# nrf52840_v2.net
KiCad netlist of a schematic drawn in Altium Designer
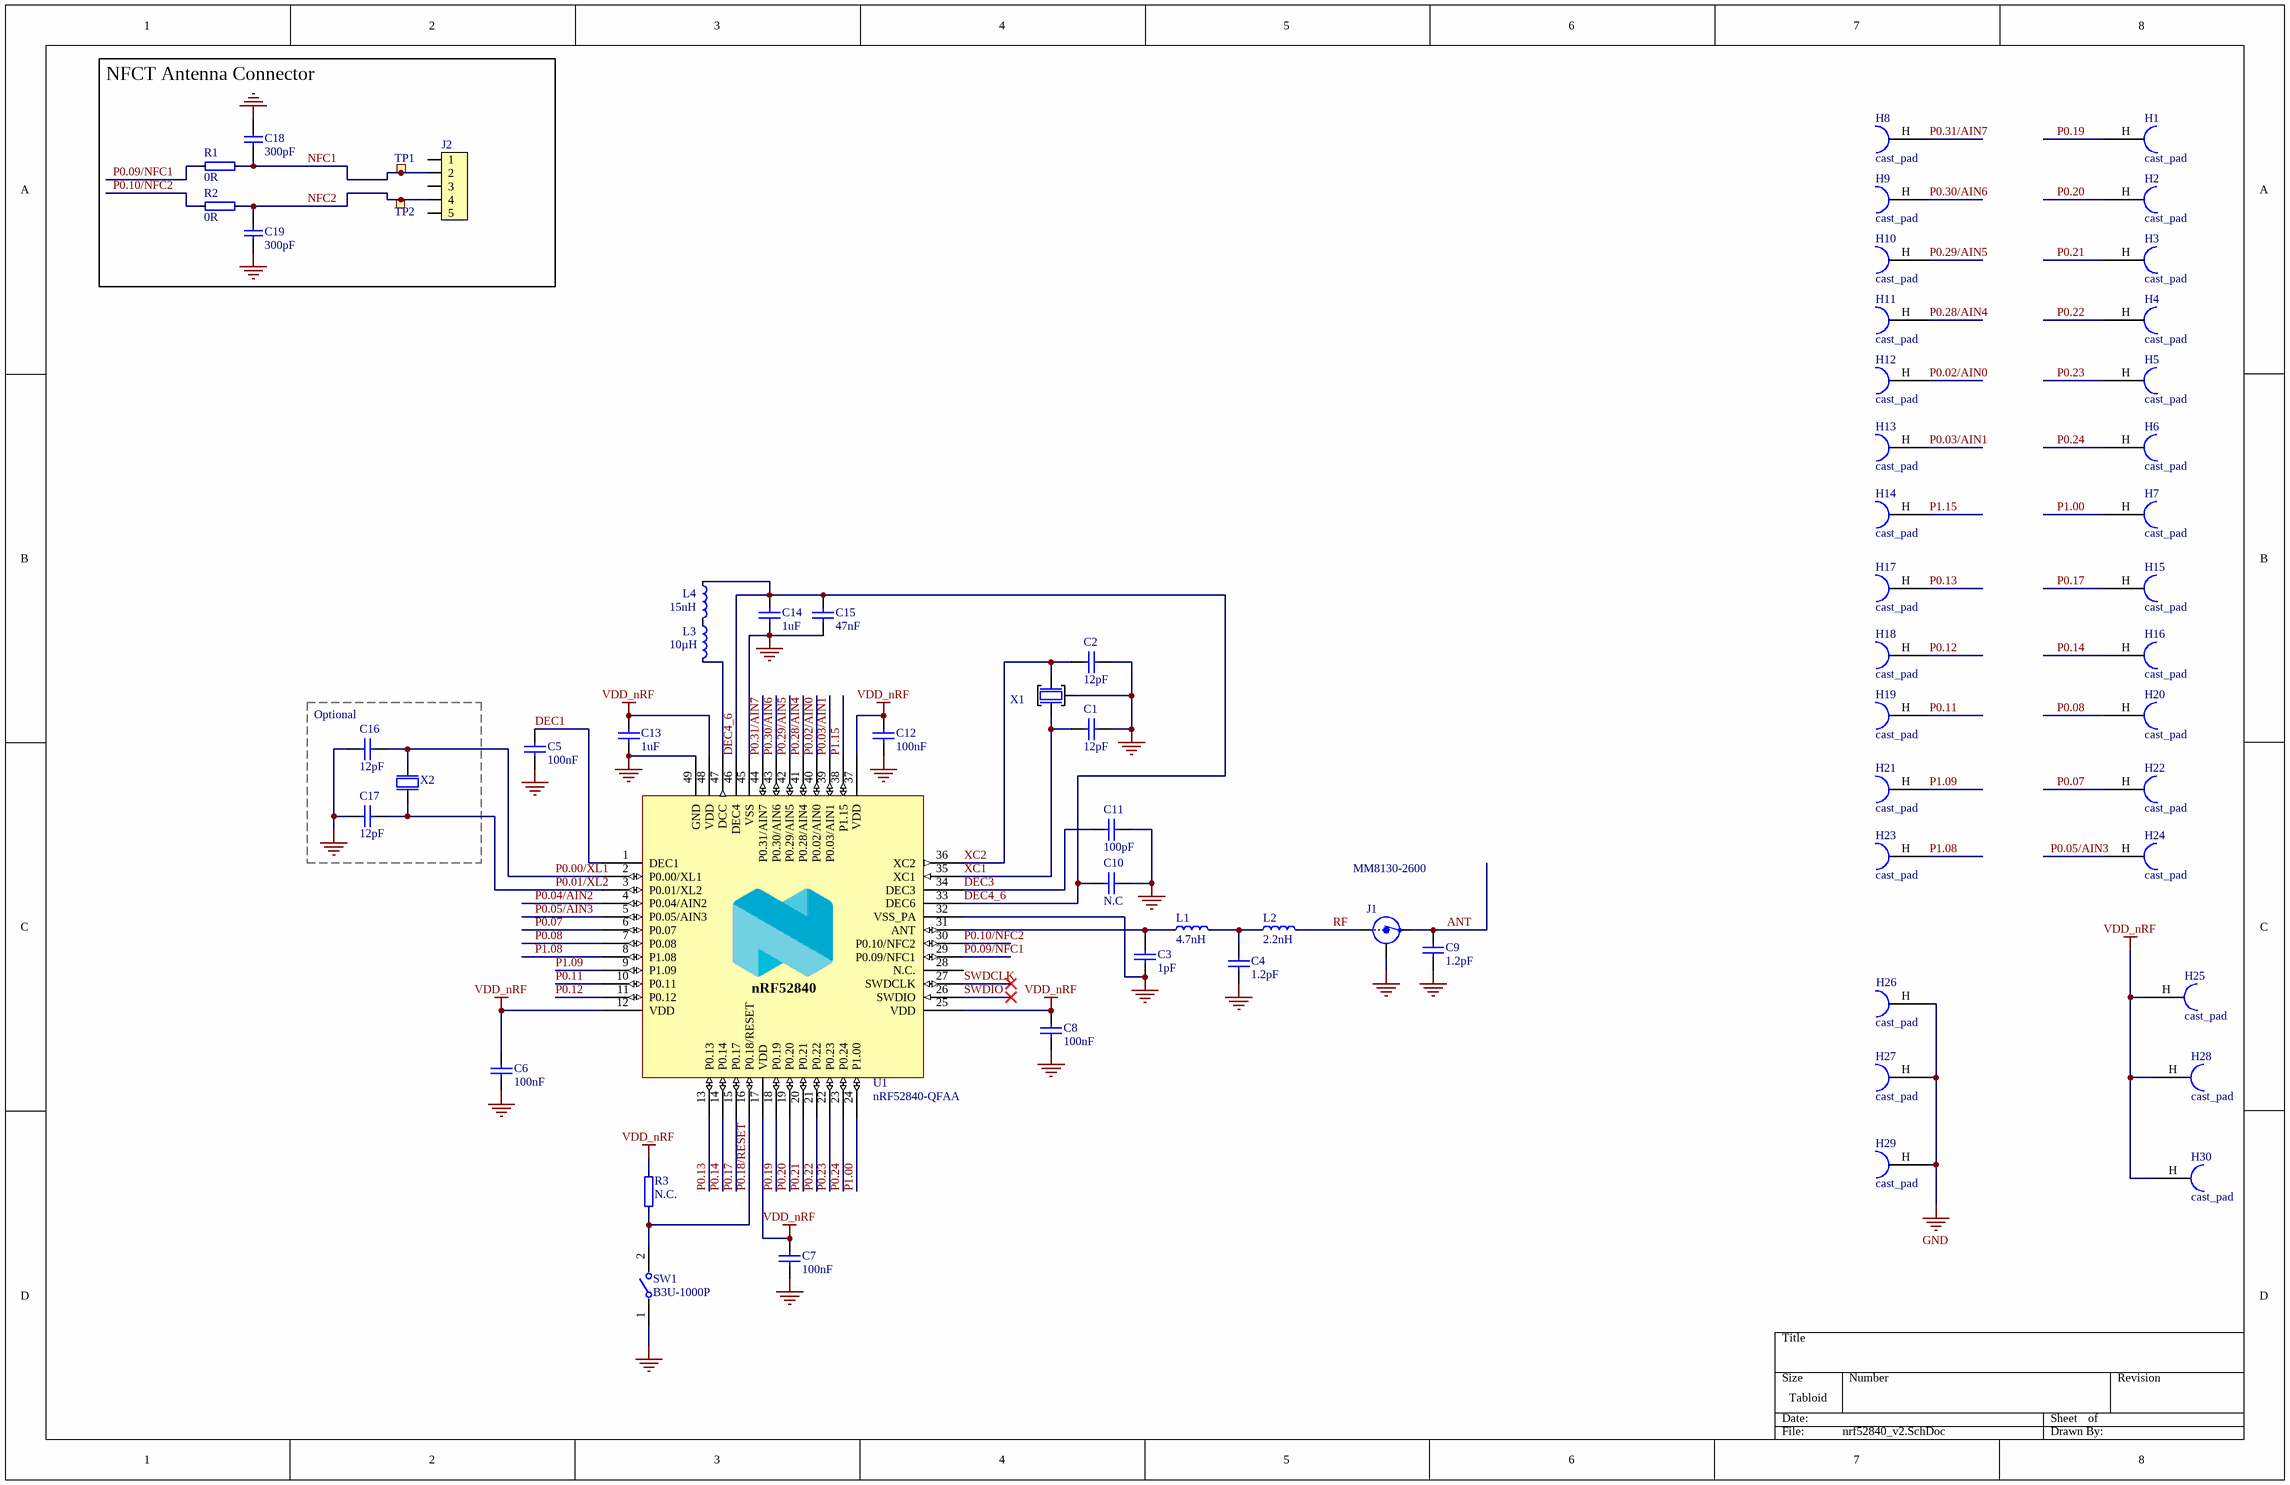
[diagram p0: nrf52840_v2.SchDoc]

(export (version "E")
  (design (tool "Eeschema 10.0.6"))
  (components
    (comp (ref "C1")
      (value "12pF")
      (footprint "CAPC1005X55X30LL05T10")
      (fields (field (name "PART NUMBER") "C0402C103K5RACTU") (field (name "MANUFACTURER") "Kemet"))
      (libsource (lib "Altium Content Vault") (part "CAP"))
    )
    (comp (ref "C2")
      (value "12pF")
      (footprint "CAPC1005X55X30LL05T10")
      (fields (field (name "PART NUMBER") "C0402C103K5RACTU") (field (name "MANUFACTURER") "Kemet"))
      (libsource (lib "Altium Content Vault") (part "CAP"))
    )
    (comp (ref "C3")
      (value "1pF")
      (footprint "CAPC1005X55X30LL05T10")
      (fields (field (name "PART NUMBER") "C0402C103K5RACTU") (field (name "MANUFACTURER") "Kemet"))
      (libsource (lib "Altium Content Vault") (part "CAP"))
    )
    (comp (ref "C4")
      (value "1.2pF")
      (footprint "CAPC1005X55X30LL05T10")
      (fields (field (name "PART NUMBER") "C0402C103K5RACTU") (field (name "MANUFACTURER") "Kemet"))
      (libsource (lib "Altium Content Vault") (part "CAP"))
    )
    (comp (ref "C5")
      (value "100nF")
      (footprint "CAPC1005X55X30LL05T10")
      (fields (field (name "PART NUMBER") "C0402C103K5RACTU") (field (name "MANUFACTURER") "Kemet"))
      (libsource (lib "Altium Content Vault") (part "CAP"))
    )
    (comp (ref "C6")
      (value "100nF")
      (footprint "CAPC1005X55X30LL05T10")
      (fields (field (name "PART NUMBER") "C0402C103K5RACTU") (field (name "MANUFACTURER") "Kemet"))
      (libsource (lib "Altium Content Vault") (part "CAP"))
    )
    (comp (ref "C7")
      (value "100nF")
      (footprint "CAPC1005X55X30LL05T10")
      (fields (field (name "PART NUMBER") "C0402C103K5RACTU") (field (name "MANUFACTURER") "Kemet"))
      (libsource (lib "Altium Content Vault") (part "CAP"))
    )
    (comp (ref "C8")
      (value "100nF")
      (footprint "CAPC1005X55X30LL05T10")
      (fields (field (name "PART NUMBER") "C0402C103K5RACTU") (field (name "MANUFACTURER") "Kemet"))
      (libsource (lib "Altium Content Vault") (part "CAP"))
    )
    (comp (ref "C9")
      (value "1.2pF")
      (footprint "CAPC1005X55X30LL05T10")
      (fields (field (name "PART NUMBER") "C0402C103K5RACTU") (field (name "MANUFACTURER") "Kemet"))
      (libsource (lib "Altium Content Vault") (part "CAP"))
    )
    (comp (ref "C10")
      (value "N.C")
      (footprint "CAPC1005X55X30LL05T10")
      (fields (field (name "PART NUMBER") "C0402C103K5RACTU") (field (name "MANUFACTURER") "Kemet"))
      (libsource (lib "Altium Content Vault") (part "CAP"))
    )
    (comp (ref "C11")
      (value "100pF")
      (footprint "CAPC1005X55X30LL05T10")
      (fields (field (name "PART NUMBER") "C0402C103K5RACTU") (field (name "MANUFACTURER") "Kemet"))
      (libsource (lib "Altium Content Vault") (part "CAP"))
    )
    (comp (ref "C12")
      (value "100nF")
      (footprint "CAPC1005X55X30LL05T10")
      (fields (field (name "PART NUMBER") "C0402C103K5RACTU") (field (name "MANUFACTURER") "Kemet"))
      (libsource (lib "Altium Content Vault") (part "CAP"))
    )
    (comp (ref "C13")
      (value "1uF")
      (footprint "CAPC1005X55X30LL05T10")
      (fields (field (name "PART NUMBER") "C0402C103K5RACTU") (field (name "MANUFACTURER") "Kemet"))
      (libsource (lib "Altium Content Vault") (part "CAP"))
    )
    (comp (ref "C14")
      (value "1uF")
      (footprint "CAPC1005X55X30LL05T10")
      (fields (field (name "PART NUMBER") "C0402C103K5RACTU") (field (name "MANUFACTURER") "Kemet"))
      (libsource (lib "Altium Content Vault") (part "CAP"))
    )
    (comp (ref "C15")
      (value "47nF")
      (footprint "CAPC1005X55X30LL05T10")
      (fields (field (name "PART NUMBER") "C0402C103K5RACTU") (field (name "MANUFACTURER") "Kemet"))
      (libsource (lib "Altium Content Vault") (part "CAP"))
    )
    (comp (ref "C16")
      (value "12pF")
      (footprint "CAPC1005X55X30LL05T10")
      (fields (field (name "PART NUMBER") "C0402C103K5RACTU") (field (name "MANUFACTURER") "Kemet"))
      (libsource (lib "Altium Content Vault") (part "CAP"))
    )
    (comp (ref "C17")
      (value "12pF")
      (footprint "CAPC1005X55X30LL05T10")
      (fields (field (name "PART NUMBER") "C0402C103K5RACTU") (field (name "MANUFACTURER") "Kemet"))
      (libsource (lib "Altium Content Vault") (part "CAP"))
    )
    (comp (ref "C18")
      (value "300pF")
      (footprint "CAPC1005X04L")
      (description "Capacitor, NP0, ±5%")
      (fields
        (field (name "PART NUMBER") "C0402-300p")
        (field (name "MANUFACTURER") "N.A.")
        (field (name "PUBLISHER") "Nordic Semiconductor")
        (field (name "AUTHOR") "rsk")
      )
      (libsource (lib "pca10056") (part "CAP"))
    )
    (comp (ref "C19")
      (value "300pF")
      (footprint "CAPC1005X04L")
      (description "Capacitor, NP0, ±5%")
      (fields
        (field (name "PART NUMBER") "C0402-300p")
        (field (name "MANUFACTURER") "N.A.")
        (field (name "PUBLISHER") "Nordic Semiconductor")
        (field (name "AUTHOR") "rsk")
      )
      (libsource (lib "pca10056") (part "CAP"))
    )
    (comp (ref "H1")
      (value "cast_pad")
      (footprint "cast_pad")
      (libsource (lib "castellated_pads") (part "cast_pad"))
    )
    (comp (ref "H2")
      (value "cast_pad")
      (footprint "cast_pad")
      (libsource (lib "castellated_pads") (part "cast_pad"))
    )
    (comp (ref "H3")
      (value "cast_pad")
      (footprint "cast_pad")
      (libsource (lib "castellated_pads") (part "cast_pad"))
    )
    (comp (ref "H4")
      (value "cast_pad")
      (footprint "cast_pad")
      (libsource (lib "castellated_pads") (part "cast_pad"))
    )
    (comp (ref "H5")
      (value "cast_pad")
      (footprint "cast_pad")
      (libsource (lib "castellated_pads") (part "cast_pad"))
    )
    (comp (ref "H6")
      (value "cast_pad")
      (footprint "cast_pad")
      (libsource (lib "castellated_pads") (part "cast_pad"))
    )
    (comp (ref "H7")
      (value "cast_pad")
      (footprint "cast_pad")
      (libsource (lib "castellated_pads") (part "cast_pad"))
    )
    (comp (ref "H8")
      (value "cast_pad")
      (footprint "cast_pad")
      (libsource (lib "castellated_pads") (part "cast_pad"))
    )
    (comp (ref "H9")
      (value "cast_pad")
      (footprint "cast_pad")
      (libsource (lib "castellated_pads") (part "cast_pad"))
    )
    (comp (ref "H10")
      (value "cast_pad")
      (footprint "cast_pad")
      (libsource (lib "castellated_pads") (part "cast_pad"))
    )
    (comp (ref "H11")
      (value "cast_pad")
      (footprint "cast_pad")
      (libsource (lib "castellated_pads") (part "cast_pad"))
    )
    (comp (ref "H12")
      (value "cast_pad")
      (footprint "cast_pad")
      (libsource (lib "castellated_pads") (part "cast_pad"))
    )
    (comp (ref "H13")
      (value "cast_pad")
      (footprint "cast_pad")
      (libsource (lib "castellated_pads") (part "cast_pad"))
    )
    (comp (ref "H14")
      (value "cast_pad")
      (footprint "cast_pad")
      (libsource (lib "castellated_pads") (part "cast_pad"))
    )
    (comp (ref "H15")
      (value "cast_pad")
      (footprint "cast_pad")
      (libsource (lib "castellated_pads") (part "cast_pad"))
    )
    (comp (ref "H16")
      (value "cast_pad")
      (footprint "cast_pad")
      (libsource (lib "castellated_pads") (part "cast_pad"))
    )
    (comp (ref "H17")
      (value "cast_pad")
      (footprint "cast_pad")
      (libsource (lib "castellated_pads") (part "cast_pad"))
    )
    (comp (ref "H18")
      (value "cast_pad")
      (footprint "cast_pad")
      (libsource (lib "castellated_pads") (part "cast_pad"))
    )
    (comp (ref "H19")
      (value "cast_pad")
      (footprint "cast_pad")
      (libsource (lib "castellated_pads") (part "cast_pad"))
    )
    (comp (ref "H20")
      (value "cast_pad")
      (footprint "cast_pad")
      (libsource (lib "castellated_pads") (part "cast_pad"))
    )
    (comp (ref "H21")
      (value "cast_pad")
      (footprint "cast_pad")
      (libsource (lib "castellated_pads") (part "cast_pad"))
    )
    (comp (ref "H22")
      (value "cast_pad")
      (footprint "cast_pad")
      (libsource (lib "castellated_pads") (part "cast_pad"))
    )
    (comp (ref "H23")
      (value "cast_pad")
      (footprint "cast_pad")
      (libsource (lib "castellated_pads") (part "cast_pad"))
    )
    (comp (ref "H24")
      (value "cast_pad")
      (footprint "cast_pad")
      (libsource (lib "castellated_pads") (part "cast_pad"))
    )
    (comp (ref "H25")
      (value "cast_pad")
      (footprint "cast_pad")
      (libsource (lib "castellated_pads") (part "cast_pad"))
    )
    (comp (ref "H26")
      (value "cast_pad")
      (footprint "cast_pad")
      (libsource (lib "castellated_pads") (part "cast_pad"))
    )
    (comp (ref "H27")
      (value "cast_pad")
      (footprint "cast_pad")
      (libsource (lib "castellated_pads") (part "cast_pad"))
    )
    (comp (ref "H28")
      (value "cast_pad")
      (footprint "cast_pad")
      (libsource (lib "castellated_pads") (part "cast_pad"))
    )
    (comp (ref "H29")
      (value "cast_pad")
      (footprint "cast_pad")
      (libsource (lib "castellated_pads") (part "cast_pad"))
    )
    (comp (ref "H30")
      (value "cast_pad")
      (footprint "cast_pad")
      (libsource (lib "castellated_pads") (part "cast_pad"))
    )
    (comp (ref "J1")
      (value "MM8130-2600")
      (footprint "COAXIAL-SWF")
      (description "Coaxial Connector with Switch")
      (fields
        (field (name "MANUFACTURER") "Murata")
        (field (name "PUBLISHER") "Nordic Semiconductor")
        (field (name "AUTHOR") "rsk")
      )
      (libsource (lib "pca10056") (part "MM8130-2600"))
    )
    (comp (ref "J2")
      (value "~")
      (footprint "FPC_05P-0.5mm-RA-SMD")
      (description "0.5mm FPC, 5P,Right Angle SMT,Double Contact,H=1.2mm,White, Tin plated")
      (fields
        (field (name "PART NUMBER") "FPC_05P-0.5mm-RA-SMD")
        (field (name "MANUFACTURER") "W-CON")
        (field (name "PUBLISHER") "Nordic Semiconductor")
        (field (name "AUTHOR") "rsk")
      )
      (libsource (lib "pca10056") (part "CONN-5"))
    )
    (comp (ref "L1")
      (value "4.7nH")
      (footprint "INDC0603X03L_C")
      (description "High frequency chip inductor ±5%")
      (fields (field (name "PART NUMBER") "L0201-4n7"))
      (libsource (lib "nrf52840_qfaa") (part "IND"))
    )
    (comp (ref "L2")
      (value "2.2nH")
      (footprint "INDC0603X03L_C")
      (description "High frequency chip inductor ±5%")
      (fields (field (name "PART NUMBER") "L0201-2n2"))
      (libsource (lib "nrf52840_qfaa") (part "IND"))
    )
    (comp (ref "L3")
      (value "10µH")
      (footprint "INDC1608X06L")
      (description "Chip inductor, IDC,min = 50 mA, ±20%")
      (fields (field (name "PART NUMBER") "L0603-10µ-TDK"))
      (libsource (lib "nrf52840_qfaa") (part "IND"))
    )
    (comp (ref "L4")
      (value "15nH")
      (footprint "INDC1005X04L")
      (description "High frequency chip inductor ±10%")
      (fields (field (name "PART NUMBER") "L0402-15n"))
      (libsource (lib "nrf52840_qfaa") (part "IND"))
    )
    (comp (ref "R1")
      (value "0R")
      (footprint "RESC1005X04L")
      (description "Resistor, ±5%, 0.063W")
      (fields
        (field (name "PART NUMBER") "R0402-0R")
        (field (name "MANUFACTURER") "N.A.")
        (field (name "PUBLISHER") "Nordic Semiconductor")
        (field (name "AUTHOR") "rsk")
      )
      (libsource (lib "pca10056") (part "RES_1"))
    )
    (comp (ref "R2")
      (value "0R")
      (footprint "RESC1005X04L")
      (description "Resistor, ±5%, 0.063W")
      (fields
        (field (name "PART NUMBER") "R0402-0R")
        (field (name "MANUFACTURER") "N.A.")
        (field (name "PUBLISHER") "Nordic Semiconductor")
        (field (name "AUTHOR") "rsk")
      )
      (libsource (lib "pca10056") (part "RES_1"))
    )
    (comp (ref "R3")
      (value "N.C.")
      (footprint "RESC1005X04L")
      (description "Not mounted")
      (fields
        (field (name "PART NUMBER") "R0402-N.C.")
        (field (name "MANUFACTURER") "N.A.")
        (field (name "PUBLISHER") "Nordic Semiconductor")
        (field (name "AUTHOR") "rsk")
      )
      (libsource (lib "pca10056") (part "R0402-N.C."))
    )
    (comp (ref "SW1")
      (value "B3U-1000P")
      (footprint "FP-B3U-1000P-MFG")
      (description "SWITCH TACTILE SPST-NO 0.05A 12V")
      (libsource (lib "Altium Content Vault") (part "ae622034201233ca1abcedc05908f33"))
    )
    (comp (ref "TP1")
      (value "Ø1.0mm,SMD")
      (footprint "TP_SMD_Ø1.0mm")
      (description "1.0mm circular SMD testpad")
      (fields
        (field (name "PART NUMBER") "TP_SMD_Ø1.0MM")
        (field (name "MANUFACTURER") "Nordic Semiconductor")
        (field (name "PUBLISHER") "Nordic Semiconductor")
        (field (name "AUTHOR") "rsk")
      )
      (libsource (lib "") (part "TESTPAD_1"))
    )
    (comp (ref "TP2")
      (value "Ø1.0mm,SMD")
      (footprint "TP_SMD_Ø1.0mm")
      (description "1.0mm circular SMD testpad")
      (fields
        (field (name "PART NUMBER") "TP_SMD_Ø1.0MM")
        (field (name "MANUFACTURER") "Nordic Semiconductor")
        (field (name "PUBLISHER") "Nordic Semiconductor")
        (field (name "AUTHOR") "rsk")
      )
      (libsource (lib "pca10056") (part "TESTPAD"))
    )
    (comp (ref "U1")
      (value "nRF52840-QFAA")
      (footprint "QFN40P600X600X90-48N")
      (description "Multi-protocol Bluetooth Low Energy, IEEE 802.15.4, ANT and 2.4GHz proprietary system-on-chip")
      (libsource (lib "nrf52840_qfaa") (part "nRF52840_QFAA"))
    )
    (comp (ref "X1")
      (value "~")
      (footprint "XTAL_2016_NT")
      (description "XTAL SMD 2016, 32MHz, Cl=8pF, Total Tol: ±30ppm")
      (fields (field (name "PART NUMBER") "XTAL_SMD2016_32MHz_8pF_General_NT"))
      (libsource (lib "nrf52840_qfaa") (part "XTAL_4-pin_NT"))
    )
    (comp (ref "X2")
      (value "~")
      (footprint "XTAL_2012")
      (description "XTAL SMD 2012, 32.768kHz, Cl=9pF, Total Tol: ±50ppm")
      (fields (field (name "PART NUMBER") "XTAL_SMD2012_32.768kHz_9pF_General"))
      (libsource (lib "nrf52840_qfaa") (part "XTAL_2-pin"))
    )
  )
  (nets
    (net (code "1") (name "/ANT") (class "Default")
      (node (ref "C9") (pin "2") (pinfunction "2_2") (pintype "passive"))
      (node (ref "J1") (pin "3") (pinfunction "OUT_3") (pintype "passive"))
    )
    (net (code "2") (name "/DEC1") (class "Default")
      (node (ref "C5") (pin "2") (pinfunction "2_2") (pintype "passive"))
      (node (ref "U1") (pin "1") (pinfunction "DEC1_1") (pintype "power_in"))
    )
    (net (code "3") (name "/DEC3") (class "Default")
      (node (ref "C11") (pin "1") (pinfunction "1_1") (pintype "passive"))
      (node (ref "U1") (pin "34") (pinfunction "DEC3_34") (pintype "power_in"))
    )
    (net (code "4") (name "/DEC4_6") (class "Default")
      (node (ref "C10") (pin "1") (pinfunction "1_1") (pintype "passive"))
      (node (ref "C14") (pin "2") (pinfunction "2_2") (pintype "passive"))
      (node (ref "C15") (pin "2") (pinfunction "2_2") (pintype "passive"))
      (node (ref "L4") (pin "1") (pinfunction "1_1") (pintype "passive"))
      (node (ref "U1") (pin "33") (pinfunction "DEC6_33") (pintype "power_in"))
      (node (ref "U1") (pin "46") (pinfunction "DEC4_46") (pintype "power_in"))
    )
    (net (code "5") (name "/NFC1") (class "Default")
      (node (ref "C18") (pin "1") (pinfunction "1_1") (pintype "passive"))
      (node (ref "J2") (pin "2") (pinfunction "2_2") (pintype "passive"))
      (node (ref "R1") (pin "1") (pinfunction "1_1") (pintype "passive"))
      (node (ref "TP1") (pin "1") (pinfunction "1_1") (pintype "passive"))
    )
    (net (code "6") (name "/NFC2") (class "Default")
      (node (ref "C19") (pin "2") (pinfunction "2_2") (pintype "passive"))
      (node (ref "J2") (pin "4") (pinfunction "4_4") (pintype "passive"))
      (node (ref "R2") (pin "1") (pinfunction "1_1") (pintype "passive"))
      (node (ref "TP2") (pin "1") (pinfunction "1_1") (pintype "passive"))
    )
    (net (code "7") (name "/P0.00{slash}XL1") (class "Default")
      (node (ref "C16") (pin "2") (pinfunction "2_2") (pintype "passive"))
      (node (ref "U1") (pin "2") (pinfunction "P0.00/XL1_2") (pintype "bidirectional"))
      (node (ref "X2") (pin "1") (pinfunction "inp_1") (pintype "passive"))
    )
    (net (code "8") (name "/P0.01{slash}XL2") (class "Default")
      (node (ref "C17") (pin "2") (pinfunction "2_2") (pintype "passive"))
      (node (ref "U1") (pin "3") (pinfunction "P0.01/XL2_3") (pintype "bidirectional"))
      (node (ref "X2") (pin "2") (pinfunction "out_2") (pintype "passive"))
    )
    (net (code "9") (name "/P0.02{slash}AIN0") (class "Default")
      (node (ref "H12") (pin "H") (pintype "passive"))
      (node (ref "U1") (pin "40") (pinfunction "P0.02/AIN0_40") (pintype "bidirectional"))
    )
    (net (code "10") (name "/P0.03{slash}AIN1") (class "Default")
      (node (ref "H13") (pin "H") (pintype "passive"))
      (node (ref "U1") (pin "39") (pinfunction "P0.03/AIN1_39") (pintype "bidirectional"))
    )
    (net (code "11") (name "/P0.04{slash}AIN2") (class "Default")
      (node (ref "U1") (pin "4") (pinfunction "P0.04/AIN2_4") (pintype "bidirectional"))
    )
    (net (code "12") (name "/P0.05{slash}AIN3") (class "Default")
      (node (ref "H24") (pin "H") (pintype "passive"))
      (node (ref "U1") (pin "5") (pinfunction "P0.05/AIN3_5") (pintype "bidirectional"))
    )
    (net (code "13") (name "/P0.07") (class "Default")
      (node (ref "H22") (pin "H") (pintype "passive"))
      (node (ref "U1") (pin "6") (pinfunction "P0.07_6") (pintype "bidirectional"))
    )
    (net (code "14") (name "/P0.08") (class "Default")
      (node (ref "H20") (pin "H") (pintype "passive"))
      (node (ref "U1") (pin "7") (pinfunction "P0.08_7") (pintype "bidirectional"))
    )
    (net (code "15") (name "/P0.09{slash}NFC1") (class "Default")
      (node (ref "R1") (pin "2") (pinfunction "2_2") (pintype "passive"))
      (node (ref "U1") (pin "29") (pinfunction "P0.09/NFC1_29") (pintype "bidirectional"))
    )
    (net (code "16") (name "/P0.10{slash}NFC2") (class "Default")
      (node (ref "R2") (pin "2") (pinfunction "2_2") (pintype "passive"))
      (node (ref "U1") (pin "30") (pinfunction "P0.10/NFC2_30") (pintype "bidirectional"))
    )
    (net (code "17") (name "/P0.11") (class "Default")
      (node (ref "H19") (pin "H") (pintype "passive"))
      (node (ref "U1") (pin "10") (pinfunction "P0.11_10") (pintype "bidirectional"))
    )
    (net (code "18") (name "/P0.12") (class "Default")
      (node (ref "H18") (pin "H") (pintype "passive"))
      (node (ref "U1") (pin "11") (pinfunction "P0.12_11") (pintype "bidirectional"))
    )
    (net (code "19") (name "/P0.13") (class "Default")
      (node (ref "H17") (pin "H") (pintype "passive"))
      (node (ref "U1") (pin "13") (pinfunction "P0.13_13") (pintype "bidirectional"))
    )
    (net (code "20") (name "/P0.14") (class "Default")
      (node (ref "H16") (pin "H") (pintype "passive"))
      (node (ref "U1") (pin "14") (pinfunction "P0.14_14") (pintype "bidirectional"))
    )
    (net (code "21") (name "/P0.17") (class "Default")
      (node (ref "H15") (pin "H") (pintype "passive"))
      (node (ref "U1") (pin "15") (pinfunction "P0.17_15") (pintype "bidirectional"))
    )
    (net (code "22") (name "/P0.18{slash}RESET") (class "Default")
      (node (ref "R3") (pin "1") (pinfunction "1_1") (pintype "passive"))
      (node (ref "SW1") (pin "2") (pinfunction "2_2") (pintype "passive"))
      (node (ref "U1") (pin "16") (pinfunction "P0.18/RESET_16") (pintype "bidirectional"))
    )
    (net (code "23") (name "/P0.19") (class "Default")
      (node (ref "H1") (pin "H") (pintype "passive"))
      (node (ref "U1") (pin "18") (pinfunction "P0.19_18") (pintype "bidirectional"))
    )
    (net (code "24") (name "/P0.20") (class "Default")
      (node (ref "H2") (pin "H") (pintype "passive"))
      (node (ref "U1") (pin "19") (pinfunction "P0.20_19") (pintype "bidirectional"))
    )
    (net (code "25") (name "/P0.21") (class "Default")
      (node (ref "H3") (pin "H") (pintype "passive"))
      (node (ref "U1") (pin "20") (pinfunction "P0.21_20") (pintype "bidirectional"))
    )
    (net (code "26") (name "/P0.22") (class "Default")
      (node (ref "H4") (pin "H") (pintype "passive"))
      (node (ref "U1") (pin "21") (pinfunction "P0.22_21") (pintype "bidirectional"))
    )
    (net (code "27") (name "/P0.23") (class "Default")
      (node (ref "H5") (pin "H") (pintype "passive"))
      (node (ref "U1") (pin "22") (pinfunction "P0.23_22") (pintype "bidirectional"))
    )
    (net (code "28") (name "/P0.24") (class "Default")
      (node (ref "H6") (pin "H") (pintype "passive"))
      (node (ref "U1") (pin "23") (pinfunction "P0.24_23") (pintype "bidirectional"))
    )
    (net (code "29") (name "/P0.28{slash}AIN4") (class "Default")
      (node (ref "H11") (pin "H") (pintype "passive"))
      (node (ref "U1") (pin "41") (pinfunction "P0.28/AIN4_41") (pintype "bidirectional"))
    )
    (net (code "30") (name "/P0.29{slash}AIN5") (class "Default")
      (node (ref "H10") (pin "H") (pintype "passive"))
      (node (ref "U1") (pin "42") (pinfunction "P0.29/AIN5_42") (pintype "bidirectional"))
    )
    (net (code "31") (name "/P0.30{slash}AIN6") (class "Default")
      (node (ref "H9") (pin "H") (pintype "passive"))
      (node (ref "U1") (pin "43") (pinfunction "P0.30/AIN6_43") (pintype "bidirectional"))
    )
    (net (code "32") (name "/P0.31{slash}AIN7") (class "Default")
      (node (ref "H8") (pin "H") (pintype "passive"))
      (node (ref "U1") (pin "44") (pinfunction "P0.31/AIN7_44") (pintype "bidirectional"))
    )
    (net (code "33") (name "/P1.00") (class "Default")
      (node (ref "H7") (pin "H") (pintype "passive"))
      (node (ref "U1") (pin "24") (pinfunction "P1.00_24") (pintype "bidirectional"))
    )
    (net (code "34") (name "/P1.08") (class "Default")
      (node (ref "H23") (pin "H") (pintype "passive"))
      (node (ref "U1") (pin "8") (pinfunction "P1.08_8") (pintype "bidirectional"))
    )
    (net (code "35") (name "/P1.09") (class "Default")
      (node (ref "H21") (pin "H") (pintype "passive"))
      (node (ref "U1") (pin "9") (pinfunction "P1.09_9") (pintype "bidirectional"))
    )
    (net (code "36") (name "/P1.15") (class "Default")
      (node (ref "H14") (pin "H") (pintype "passive"))
      (node (ref "U1") (pin "38") (pinfunction "P1.15_38") (pintype "bidirectional"))
    )
    (net (code "37") (name "/RF") (class "Default")
      (node (ref "J1") (pin "1") (pinfunction "IN_1") (pintype "passive"))
      (node (ref "L2") (pin "2") (pinfunction "2_2") (pintype "passive"))
    )
    (net (code "38") (name "/SWDCLK") (class "Default")
      (node (ref "U1") (pin "27") (pinfunction "SWDCLK_27") (pintype "bidirectional+no_connect"))
    )
    (net (code "39") (name "/SWDIO") (class "Default")
      (node (ref "U1") (pin "26") (pinfunction "SWDIO_26") (pintype "input+no_connect"))
    )
    (net (code "40") (name "/XC1") (class "Default")
      (node (ref "C1") (pin "1") (pinfunction "1_1") (pintype "passive"))
      (node (ref "U1") (pin "35") (pinfunction "XC1_35") (pintype "input"))
      (node (ref "X1") (pin "1") (pinfunction "IN_1") (pintype "passive"))
    )
    (net (code "41") (name "/XC2") (class "Default")
      (node (ref "C2") (pin "1") (pinfunction "1_1") (pintype "passive"))
      (node (ref "U1") (pin "36") (pinfunction "XC2_36") (pintype "output"))
      (node (ref "X1") (pin "3") (pinfunction "OUT_3") (pintype "passive"))
    )
    (net (code "42") (name "GND") (class "Default")
      (node (ref "C1") (pin "2") (pinfunction "2_2") (pintype "passive"))
      (node (ref "C10") (pin "2") (pinfunction "2_2") (pintype "passive"))
      (node (ref "C11") (pin "2") (pinfunction "2_2") (pintype "passive"))
      (node (ref "C12") (pin "1") (pinfunction "1_1") (pintype "passive"))
      (node (ref "C13") (pin "1") (pinfunction "1_1") (pintype "passive"))
      (node (ref "C14") (pin "1") (pinfunction "1_1") (pintype "passive"))
      (node (ref "C15") (pin "1") (pinfunction "1_1") (pintype "passive"))
      (node (ref "C16") (pin "1") (pinfunction "1_1") (pintype "passive"))
      (node (ref "C17") (pin "1") (pinfunction "1_1") (pintype "passive"))
      (node (ref "C18") (pin "2") (pinfunction "2_2") (pintype "passive"))
      (node (ref "C19") (pin "1") (pinfunction "1_1") (pintype "passive"))
      (node (ref "C2") (pin "2") (pinfunction "2_2") (pintype "passive"))
      (node (ref "C3") (pin "1") (pinfunction "1_1") (pintype "passive"))
      (node (ref "C4") (pin "1") (pinfunction "1_1") (pintype "passive"))
      (node (ref "C5") (pin "1") (pinfunction "1_1") (pintype "passive"))
      (node (ref "C6") (pin "1") (pinfunction "1_1") (pintype "passive"))
      (node (ref "C7") (pin "1") (pinfunction "1_1") (pintype "passive"))
      (node (ref "C8") (pin "1") (pinfunction "1_1") (pintype "passive"))
      (node (ref "C9") (pin "1") (pinfunction "1_1") (pintype "passive"))
      (node (ref "H26") (pin "H") (pintype "passive"))
      (node (ref "H27") (pin "H") (pintype "passive"))
      (node (ref "H29") (pin "H") (pintype "passive"))
      (node (ref "J1") (pin "2") (pinfunction "Shield_2") (pintype "passive"))
      (node (ref "SW1") (pin "1") (pinfunction "1_1") (pintype "passive"))
      (node (ref "U1") (pin "32") (pinfunction "VSS_PA_32") (pintype "power_in"))
      (node (ref "U1") (pin "45") (pinfunction "VSS_45") (pintype "power_in"))
      (node (ref "U1") (pin "49") (pinfunction "GND_49") (pintype "power_in"))
      (node (ref "X1") (pin "2") (pinfunction "GND_2") (pintype "passive"))
    )
    (net (code "43") (name "Net-(C4-Pad2)") (class "Default")
      (node (ref "C4") (pin "2") (pinfunction "2_2") (pintype "passive"))
      (node (ref "L1") (pin "2") (pinfunction "2_2") (pintype "passive"))
      (node (ref "L2") (pin "1") (pinfunction "1_1") (pintype "passive"))
    )
    (net (code "44") (name "Net-(L3-Pad1)") (class "Default")
      (node (ref "L3") (pin "1") (pinfunction "1_1") (pintype "passive"))
      (node (ref "L4") (pin "2") (pinfunction "2_2") (pintype "passive"))
    )
    (net (code "45") (name "Net-(U1-ANT)") (class "Default")
      (node (ref "C3") (pin "2") (pinfunction "2_2") (pintype "passive"))
      (node (ref "L1") (pin "1") (pinfunction "1_1") (pintype "passive"))
      (node (ref "U1") (pin "31") (pinfunction "ANT_31") (pintype "bidirectional"))
    )
    (net (code "46") (name "Net-(U1-DCC)") (class "Default")
      (node (ref "L3") (pin "2") (pinfunction "2_2") (pintype "passive"))
      (node (ref "U1") (pin "47") (pinfunction "DCC_47") (pintype "output"))
    )
    (net (code "47") (name "VDD_nRF") (class "Default")
      (node (ref "C12") (pin "2") (pinfunction "2_2") (pintype "passive"))
      (node (ref "C13") (pin "2") (pinfunction "2_2") (pintype "passive"))
      (node (ref "C6") (pin "2") (pinfunction "2_2") (pintype "passive"))
      (node (ref "C7") (pin "2") (pinfunction "2_2") (pintype "passive"))
      (node (ref "C8") (pin "2") (pinfunction "2_2") (pintype "passive"))
      (node (ref "H25") (pin "H") (pintype "passive"))
      (node (ref "H28") (pin "H") (pintype "passive"))
      (node (ref "H30") (pin "H") (pintype "passive"))
      (node (ref "R3") (pin "2") (pinfunction "2_2") (pintype "passive"))
      (node (ref "U1") (pin "12") (pinfunction "VDD_12") (pintype "power_in"))
      (node (ref "U1") (pin "17") (pinfunction "VDD_17") (pintype "power_in"))
      (node (ref "U1") (pin "25") (pinfunction "VDD_25") (pintype "power_in"))
      (node (ref "U1") (pin "37") (pinfunction "VDD_37") (pintype "power_in"))
      (node (ref "U1") (pin "48") (pinfunction "VDD_48") (pintype "power_in"))
    )
    (net (code "48") (name "unconnected-(J2-Pad1)") (class "Default")
      (node (ref "J2") (pin "1") (pinfunction "1_1") (pintype "passive"))
    )
    (net (code "49") (name "unconnected-(J2-Pad3)") (class "Default")
      (node (ref "J2") (pin "3") (pinfunction "3_3") (pintype "passive"))
    )
    (net (code "50") (name "unconnected-(J2-Pad5)") (class "Default")
      (node (ref "J2") (pin "5") (pinfunction "5_5") (pintype "passive"))
    )
    (net (code "51") (name "unconnected-(U1-N.C.-Pad28)") (class "Default")
      (node (ref "U1") (pin "28") (pinfunction "N.C._28") (pintype "passive"))
    )
  )
)
